# soic-8-breakout-board.net
KiCad netlist of a schematic drawn in Altium Designer
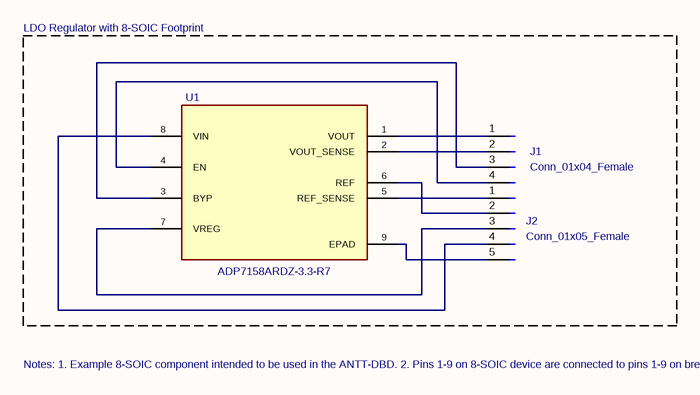
[diagram p0: soic-8-breakout-board.SchDoc]

(export (version "E")
  (design (tool "Eeschema 10.0.6"))
  (components
    (comp (ref "J1") (value "Conn_01x04_Female") (libsource (lib "Connector") (part "Conn_01x04_Female")))
    (comp (ref "J2") (value "Conn_01x05_Female") (libsource (lib "Connector") (part "Conn_01x05_Female")))
    (comp (ref "U1")
      (value "ADP7158ARDZ-3.3-R7")
      (fields (field (name "MANUFACTURER") "ANALOG DEVICES"))
      (libsource (lib "ADP7158ARDZ-3") (part "ADP7158ARDZ-3.3-R7"))
    )
  )
  (nets
    (net (code "1") (name "Net-(J1-Pin_1)") (class "Default")
      (node (ref "J1") (pin "1") (pinfunction "Pin_1_1") (pintype "passive"))
      (node (ref "U1") (pin "1") (pinfunction "VOUT_1") (pintype "passive"))
    )
    (net (code "2") (name "Net-(J1-Pin_2)") (class "Default")
      (node (ref "J1") (pin "2") (pinfunction "Pin_2_2") (pintype "passive"))
      (node (ref "U1") (pin "2") (pinfunction "VOUT_SENSE_2") (pintype "passive"))
    )
    (net (code "3") (name "Net-(J1-Pin_3)") (class "Default")
      (node (ref "J1") (pin "3") (pinfunction "Pin_3_3") (pintype "passive"))
      (node (ref "U1") (pin "3") (pinfunction "BYP_3") (pintype "passive"))
    )
    (net (code "4") (name "Net-(J1-Pin_4)") (class "Default")
      (node (ref "J1") (pin "4") (pinfunction "Pin_4_4") (pintype "passive"))
      (node (ref "U1") (pin "4") (pinfunction "EN_4") (pintype "passive"))
    )
    (net (code "5") (name "Net-(J2-Pin_1)") (class "Default")
      (node (ref "J2") (pin "1") (pinfunction "Pin_1_1") (pintype "passive"))
      (node (ref "U1") (pin "5") (pinfunction "REF_SENSE_5") (pintype "passive"))
    )
    (net (code "6") (name "Net-(J2-Pin_2)") (class "Default")
      (node (ref "J2") (pin "2") (pinfunction "Pin_2_2") (pintype "passive"))
      (node (ref "U1") (pin "6") (pinfunction "REF_6") (pintype "passive"))
    )
    (net (code "7") (name "Net-(J2-Pin_3)") (class "Default")
      (node (ref "J2") (pin "3") (pinfunction "Pin_3_3") (pintype "passive"))
      (node (ref "U1") (pin "7") (pinfunction "VREG_7") (pintype "passive"))
    )
    (net (code "8") (name "Net-(J2-Pin_4)") (class "Default")
      (node (ref "J2") (pin "4") (pinfunction "Pin_4_4") (pintype "passive"))
      (node (ref "U1") (pin "8") (pinfunction "VIN_8") (pintype "passive"))
    )
    (net (code "9") (name "Net-(J2-Pin_5)") (class "Default")
      (node (ref "J2") (pin "5") (pinfunction "Pin_5_5") (pintype "passive"))
      (node (ref "U1") (pin "9") (pinfunction "EPAD_9") (pintype "passive"))
    )
  )
)
